# cociclo_placeCommune.net
KiCad netlist of a schematic drawn in EAGLE
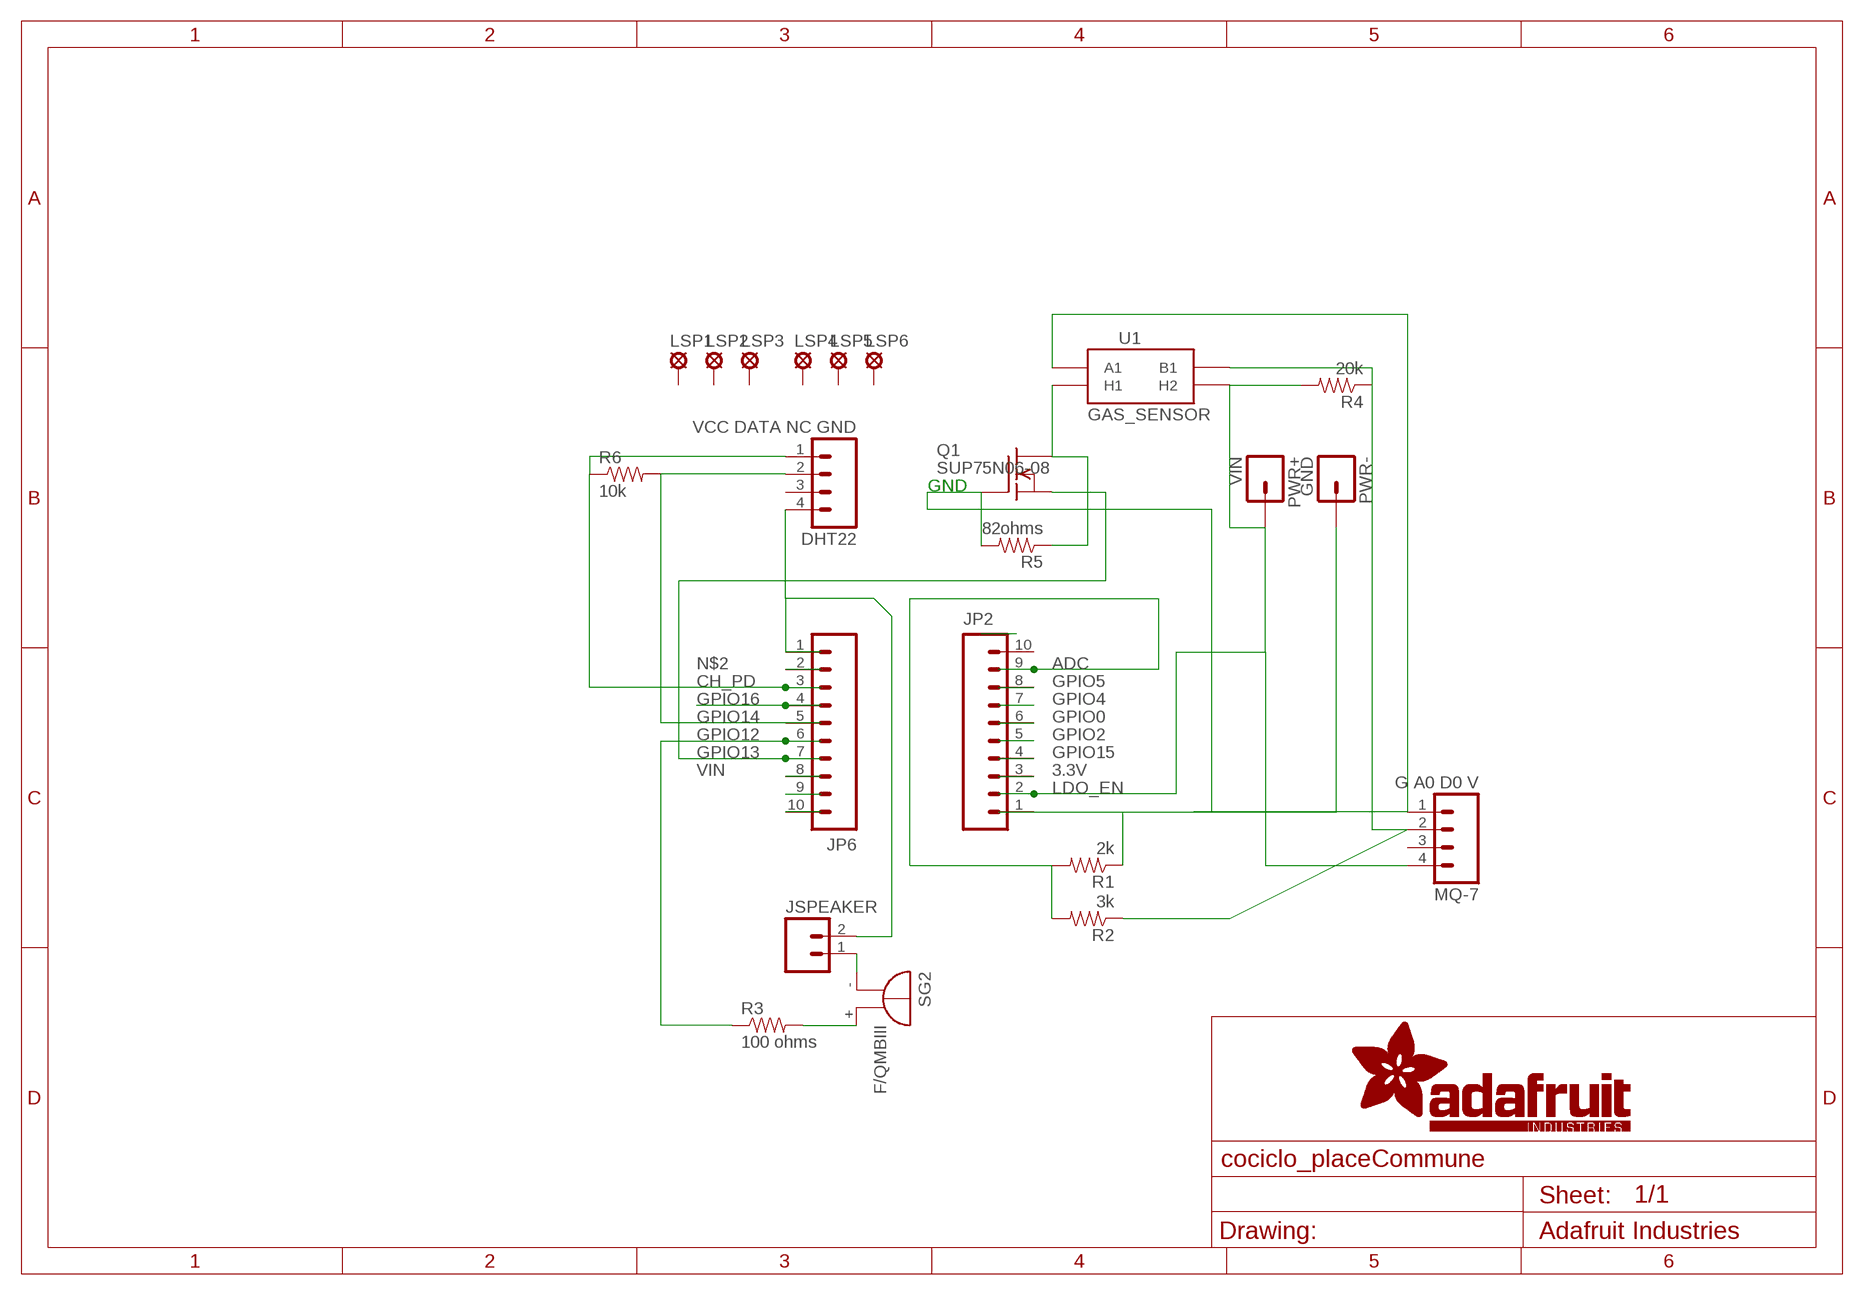
[diagram p0: schematic, sheet 1]

(export (version "E")
  (design (tool "Eeschema 10.0.6"))
  (components
    (comp (ref "DHT22")
      (value "VCC DATA NC GND")
      (footprint "eagle-import:1X04")
      (libsource (lib "eagle-import") (part "M04PTH"))
    )
    (comp (ref "JP2")
      (value "M10SILK_FEMALE_PTH")
      (footprint "eagle-import:1X10")
      (libsource (lib "eagle-import") (part "M10SILK_FEMALE_PTH"))
    )
    (comp (ref "JP6")
      (value "M10SILK_FEMALE_PTH")
      (footprint "eagle-import:1X10")
      (libsource (lib "eagle-import") (part "M10SILK_FEMALE_PTH"))
    )
    (comp (ref "JSPEAKER")
      (value "M02PTH")
      (footprint "eagle-import:1X02")
      (libsource (lib "eagle-import") (part "M02PTH"))
    )
    (comp (ref "LSP1")
      (value "LSP10")
      (footprint "eagle-import:LSP10")
      (libsource (lib "eagle-import") (part "LSP10"))
    )
    (comp (ref "LSP2")
      (value "LSP10")
      (footprint "eagle-import:LSP10")
      (libsource (lib "eagle-import") (part "LSP10"))
    )
    (comp (ref "LSP3")
      (value "LSP10")
      (footprint "eagle-import:LSP10")
      (libsource (lib "eagle-import") (part "LSP10"))
    )
    (comp (ref "LSP4")
      (value "LSP10")
      (footprint "eagle-import:LSP10")
      (libsource (lib "eagle-import") (part "LSP10"))
    )
    (comp (ref "LSP5")
      (value "LSP10")
      (footprint "eagle-import:LSP10")
      (libsource (lib "eagle-import") (part "LSP10"))
    )
    (comp (ref "LSP6")
      (value "LSP10")
      (footprint "eagle-import:LSP10")
      (libsource (lib "eagle-import") (part "LSP10"))
    )
    (comp (ref "MQ-7")
      (value "G A0 D0 V")
      (footprint "eagle-import:1X04")
      (libsource (lib "eagle-import") (part "M04PTH"))
    )
    (comp (ref "PWR+")
      (value "VIN")
      (footprint "eagle-import:1X01NS-KIT")
      (libsource (lib "eagle-import") (part "M01NOSILK-KIT"))
    )
    (comp (ref "PWR-")
      (value "GND")
      (footprint "eagle-import:1X01NS-KIT")
      (libsource (lib "eagle-import") (part "M01NOSILK-KIT"))
    )
    (comp (ref "Q1")
      (value "SUP75N06-08")
      (footprint "eagle-import:TO220")
      (libsource (lib "eagle-import") (part "SUP75N06-08"))
    )
    (comp (ref "R1")
      (value "2k")
      (footprint "eagle-import:1206")
      (libsource (lib "eagle-import") (part "RESISTOR1206"))
    )
    (comp (ref "R2")
      (value "3k")
      (footprint "eagle-import:1206")
      (libsource (lib "eagle-import") (part "RESISTOR1206"))
    )
    (comp (ref "R3")
      (value "100 ohms")
      (footprint "eagle-import:1206")
      (libsource (lib "eagle-import") (part "RESISTOR1206"))
    )
    (comp (ref "R4")
      (value "20k")
      (footprint "eagle-import:1206")
      (libsource (lib "eagle-import") (part "RESISTOR1206"))
    )
    (comp (ref "R5")
      (value "82ohms")
      (footprint "eagle-import:1206")
      (libsource (lib "eagle-import") (part "RESISTOR1206"))
    )
    (comp (ref "R6")
      (value "10k")
      (footprint "eagle-import:1206")
      (libsource (lib "eagle-import") (part "RESISTOR1206"))
    )
    (comp (ref "SG2")
      (value "F/QMBIII")
      (footprint "eagle-import:F_QMBIII")
      (libsource (lib "eagle-import") (part "F/QMBIII"))
    )
    (comp (ref "U1")
      (value "GAS_SENSOR")
      (footprint "eagle-import:MQ-3")
      (libsource (lib "eagle-import") (part "GAS_SENSOR"))
    )
  )
  (nets
    (net (code "1") (name "/3.3V") (class "Default")
      (node (ref "JP2") (pin "3") (pinfunction "3_3") (pintype "passive"))
    )
    (net (code "2") (name "/ADC") (class "Default")
      (node (ref "JP2") (pin "9") (pinfunction "9_9") (pintype "passive"))
      (node (ref "R1") (pin "2") (pinfunction "2_2") (pintype "passive"))
      (node (ref "R2") (pin "2") (pinfunction "2_2") (pintype "passive"))
    )
    (net (code "3") (name "/CH_PD") (class "Default")
      (node (ref "DHT22") (pin "1") (pinfunction "1_1") (pintype "passive"))
      (node (ref "JP6") (pin "3") (pinfunction "3_3") (pintype "passive"))
      (node (ref "R6") (pin "1") (pinfunction "1_1") (pintype "passive"))
    )
    (net (code "4") (name "/GND") (class "Default")
      (node (ref "JP2") (pin "1") (pinfunction "1_1") (pintype "passive"))
      (node (ref "JP6") (pin "10") (pinfunction "10_10") (pintype "passive"))
      (node (ref "MQ-7") (pin "1") (pinfunction "1_1") (pintype "passive"))
      (node (ref "PWR-") (pin "1") (pinfunction "1_1") (pintype "passive"))
      (node (ref "Q1") (pin "1") (pinfunction "G_1") (pintype "passive"))
      (node (ref "R1") (pin "1") (pinfunction "1_1") (pintype "passive"))
      (node (ref "R5") (pin "2") (pinfunction "2_2") (pintype "passive"))
      (node (ref "U1") (pin "A1") (pinfunction "A1_A1") (pintype "bidirectional"))
    )
    (net (code "5") (name "/GPIO0") (class "Default")
      (node (ref "JP2") (pin "6") (pinfunction "6_6") (pintype "passive"))
    )
    (net (code "6") (name "/GPIO2") (class "Default")
      (node (ref "JP2") (pin "5") (pinfunction "5_5") (pintype "passive"))
    )
    (net (code "7") (name "/GPIO4") (class "Default")
      (node (ref "JP2") (pin "7") (pinfunction "7_7") (pintype "passive"))
    )
    (net (code "8") (name "/GPIO5") (class "Default")
      (node (ref "JP2") (pin "8") (pinfunction "8_8") (pintype "passive"))
    )
    (net (code "9") (name "/GPIO12") (class "Default")
      (node (ref "JP6") (pin "6") (pinfunction "6_6") (pintype "passive"))
      (node (ref "R3") (pin "1") (pinfunction "1_1") (pintype "passive"))
    )
    (net (code "10") (name "/GPIO13") (class "Default")
      (node (ref "JP6") (pin "7") (pinfunction "7_7") (pintype "passive"))
      (node (ref "Q1") (pin "3") (pinfunction "S_3") (pintype "passive"))
    )
    (net (code "11") (name "/GPIO14") (class "Default")
      (node (ref "DHT22") (pin "2") (pinfunction "2_2") (pintype "passive"))
      (node (ref "JP6") (pin "5") (pinfunction "5_5") (pintype "passive"))
      (node (ref "R6") (pin "2") (pinfunction "2_2") (pintype "passive"))
    )
    (net (code "12") (name "/GPIO15") (class "Default")
      (node (ref "JP2") (pin "4") (pinfunction "4_4") (pintype "passive"))
    )
    (net (code "13") (name "/GPIO16") (class "Default")
      (node (ref "JP6") (pin "4") (pinfunction "4_4") (pintype "passive"))
    )
    (net (code "14") (name "/LDO_EN") (class "Default")
      (node (ref "JP2") (pin "2") (pinfunction "2_2") (pintype "passive"))
      (node (ref "MQ-7") (pin "4") (pinfunction "4_4") (pintype "passive"))
      (node (ref "PWR+") (pin "1") (pinfunction "1_1") (pintype "passive"))
      (node (ref "R4") (pin "2") (pinfunction "2_2") (pintype "passive"))
      (node (ref "U1") (pin "HB") (pinfunction "H2_HB") (pintype "bidirectional"))
    )
    (net (code "15") (name "/N$2") (class "Default")
      (node (ref "JP6") (pin "2") (pinfunction "2_2") (pintype "passive"))
    )
    (net (code "16") (name "/VIN") (class "Default")
      (node (ref "JP6") (pin "8") (pinfunction "8_8") (pintype "passive"))
    )
    (net (code "17") (name "Net-(DHT22-Pad4)") (class "Default")
      (node (ref "DHT22") (pin "4") (pinfunction "4_4") (pintype "passive"))
      (node (ref "JP6") (pin "1") (pinfunction "1_1") (pintype "passive"))
      (node (ref "JSPEAKER") (pin "2") (pinfunction "2_2") (pintype "passive"))
    )
    (net (code "18") (name "Net-(MQ-7-Pad2)") (class "Default")
      (node (ref "MQ-7") (pin "2") (pinfunction "2_2") (pintype "passive"))
      (node (ref "R2") (pin "1") (pinfunction "1_1") (pintype "passive"))
      (node (ref "R4") (pin "1") (pinfunction "1_1") (pintype "passive"))
      (node (ref "U1") (pin "B1") (pinfunction "B1_B1") (pintype "bidirectional"))
    )
    (net (code "19") (name "Net-(Q1-D)") (class "Default")
      (node (ref "Q1") (pin "2") (pinfunction "D_2") (pintype "passive"))
      (node (ref "R5") (pin "1") (pinfunction "1_1") (pintype "passive"))
      (node (ref "U1") (pin "HA") (pinfunction "H1_HA") (pintype "bidirectional"))
    )
    (net (code "20") (name "Net-(SG2-+)") (class "Default")
      (node (ref "JSPEAKER") (pin "1") (pinfunction "1_1") (pintype "passive"))
      (node (ref "SG2") (pin "-") (pinfunction "+_-") (pintype "passive"))
    )
    (net (code "21") (name "Net-(SG2--)") (class "Default")
      (node (ref "R3") (pin "2") (pinfunction "2_2") (pintype "passive"))
      (node (ref "SG2") (pin "+") (pinfunction "-_+") (pintype "passive"))
    )
    (net (code "22") (name "unconnected-(DHT22-Pad3)") (class "Default")
      (node (ref "DHT22") (pin "3") (pinfunction "3_3") (pintype "passive"))
    )
    (net (code "23") (name "unconnected-(JP2-Pad10)") (class "Default")
      (node (ref "JP2") (pin "10") (pinfunction "10_10") (pintype "passive"))
    )
    (net (code "24") (name "unconnected-(JP6-Pad9)") (class "Default")
      (node (ref "JP6") (pin "9") (pinfunction "9_9") (pintype "passive"))
    )
    (net (code "25") (name "unconnected-(LSP1-PadMP)") (class "Default")
      (node (ref "LSP1") (pin "MP") (pinfunction "MP_MP") (pintype "passive"))
    )
    (net (code "26") (name "unconnected-(LSP2-PadMP)") (class "Default")
      (node (ref "LSP2") (pin "MP") (pinfunction "MP_MP") (pintype "passive"))
    )
    (net (code "27") (name "unconnected-(LSP3-PadMP)") (class "Default")
      (node (ref "LSP3") (pin "MP") (pinfunction "MP_MP") (pintype "passive"))
    )
    (net (code "28") (name "unconnected-(LSP4-PadMP)") (class "Default")
      (node (ref "LSP4") (pin "MP") (pinfunction "MP_MP") (pintype "passive"))
    )
    (net (code "29") (name "unconnected-(LSP5-PadMP)") (class "Default")
      (node (ref "LSP5") (pin "MP") (pinfunction "MP_MP") (pintype "passive"))
    )
    (net (code "30") (name "unconnected-(LSP6-PadMP)") (class "Default")
      (node (ref "LSP6") (pin "MP") (pinfunction "MP_MP") (pintype "passive"))
    )
    (net (code "31") (name "unconnected-(MQ-7-Pad3)") (class "Default")
      (node (ref "MQ-7") (pin "3") (pinfunction "3_3") (pintype "passive"))
    )
  )
)
